# owl_digital.net
KiCad netlist of a schematic drawn in EAGLE
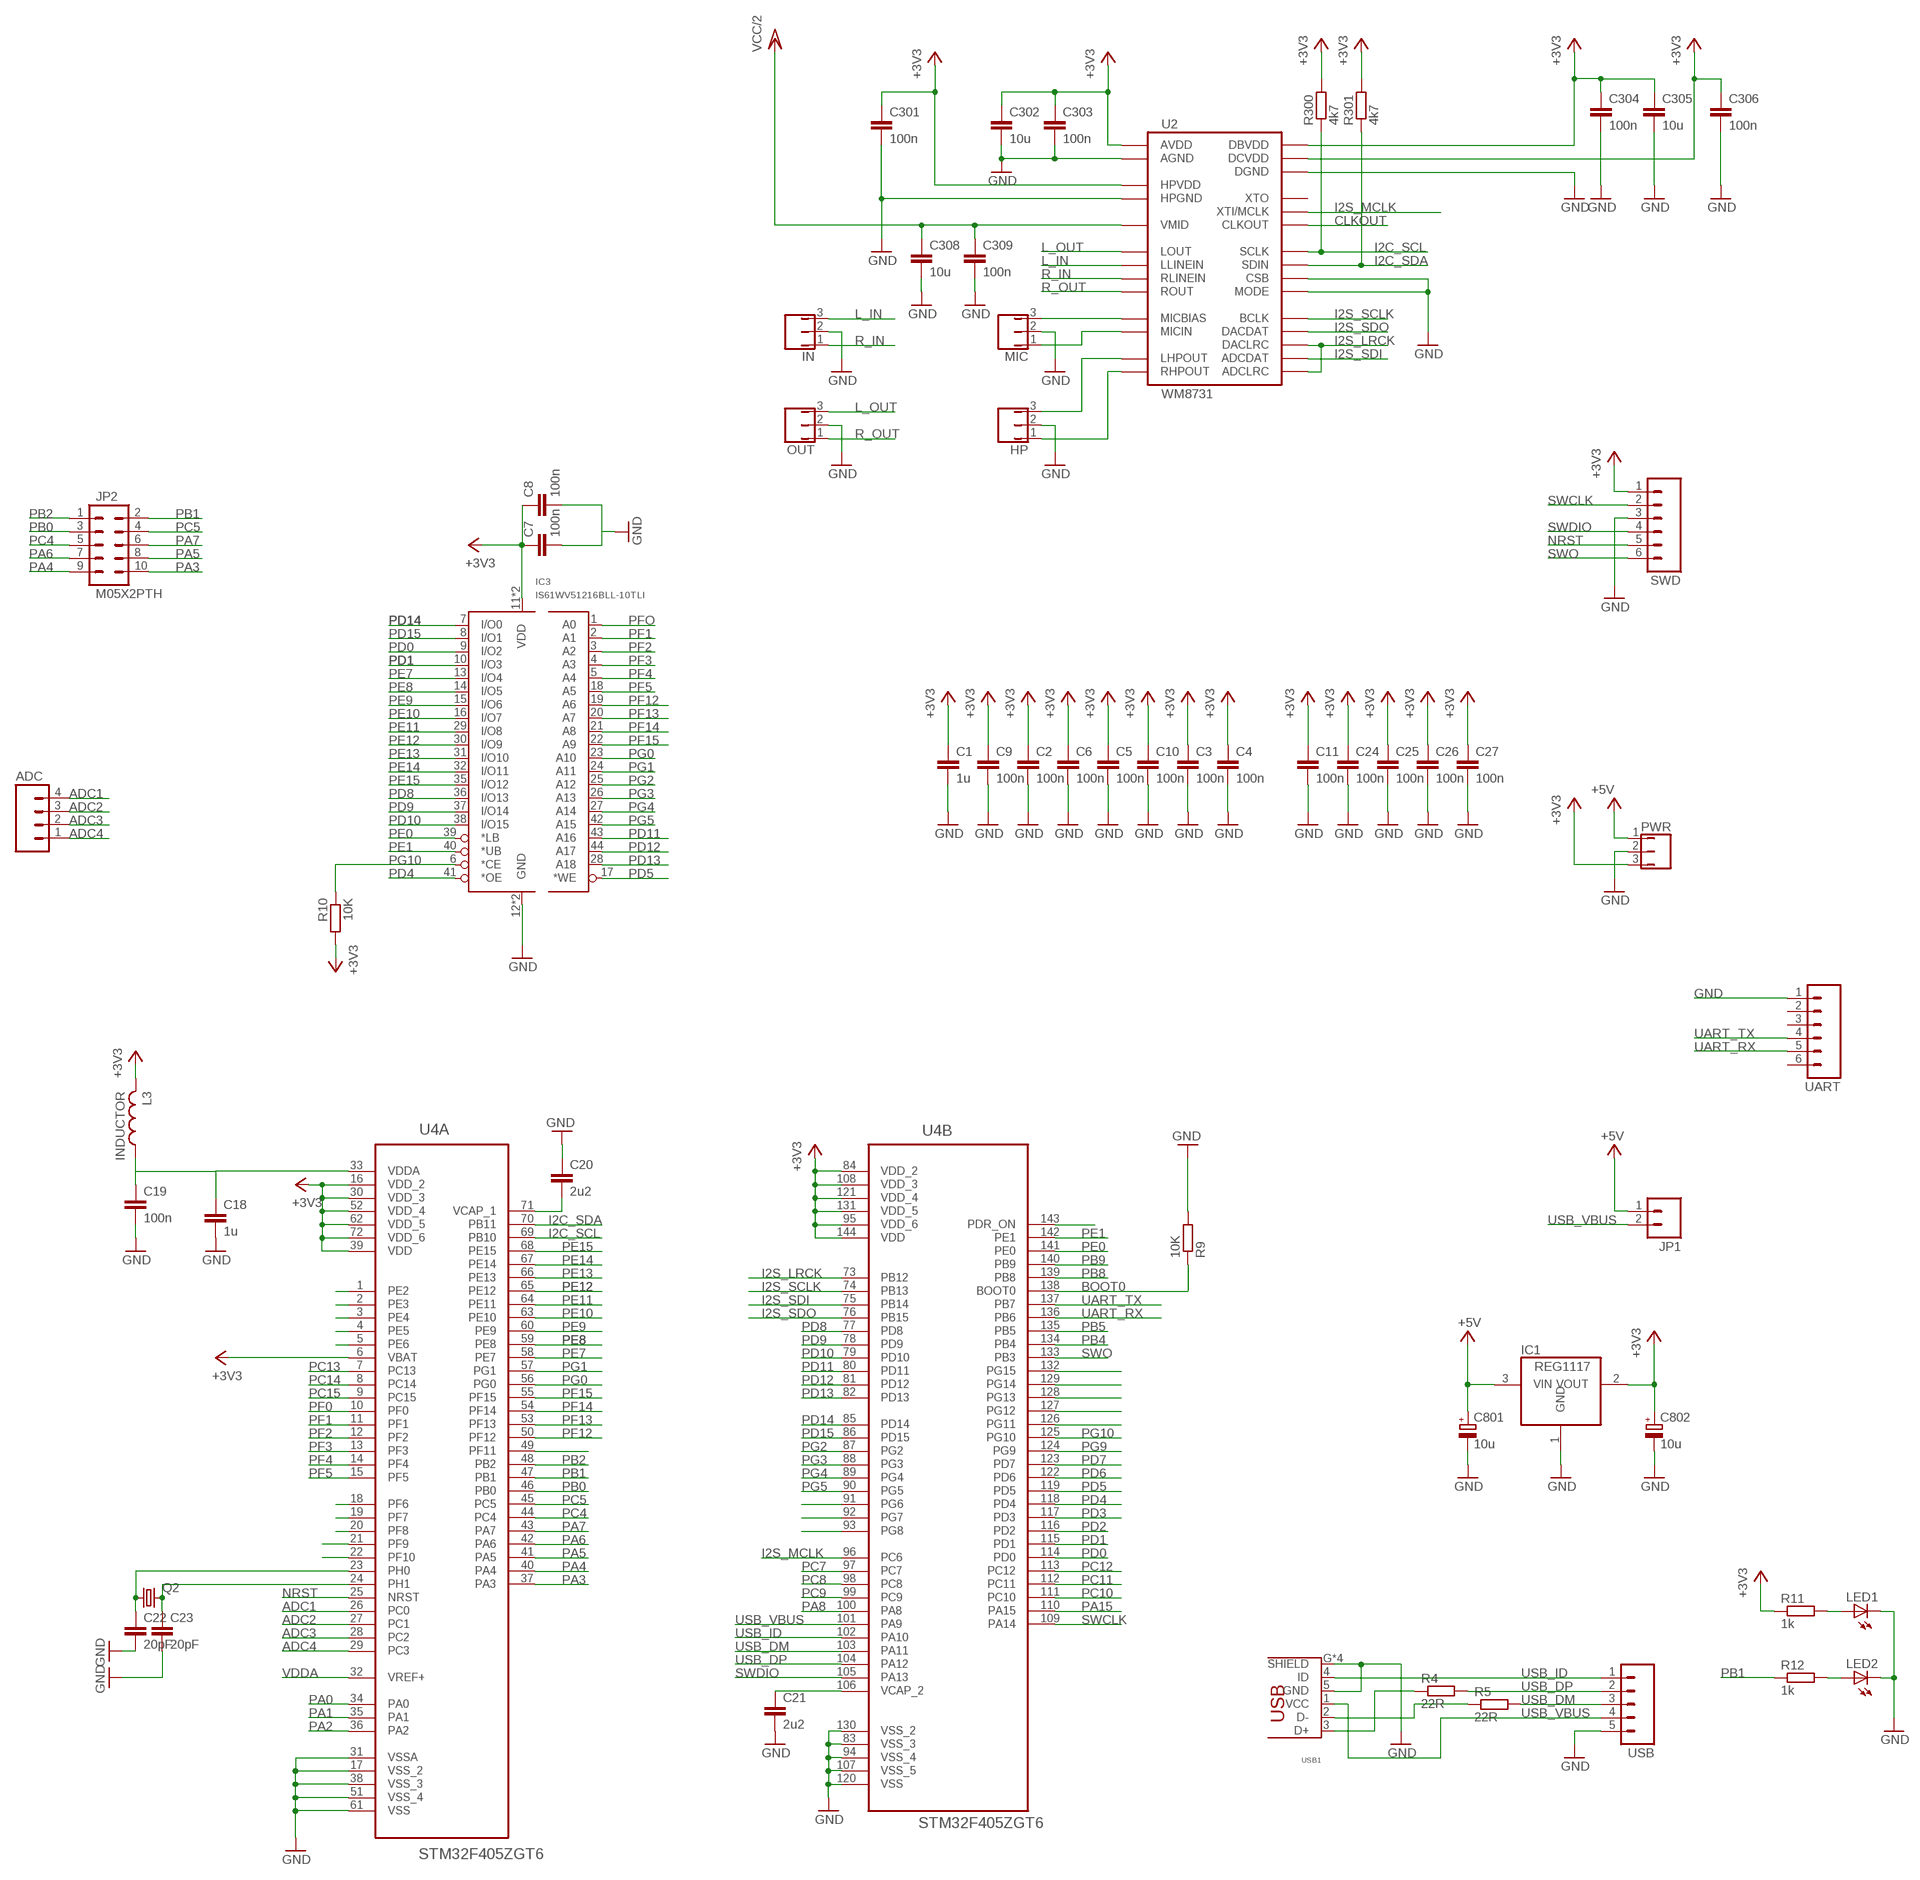
[diagram p0: schematic, sheet 1]

(export (version "E")
  (design (tool "Eeschema 10.0.6"))
  (components
    (comp (ref "ADC")
      (value "M04PTH")
      (footprint "eagle-import:1X04")
      (libsource (lib "eagle-import") (part "M04PTH"))
    )
    (comp (ref "C1")
      (value "1u")
      (footprint "eagle-import:C0603")
      (libsource (lib "eagle-import") (part "C-EUC0603"))
    )
    (comp (ref "C2")
      (value "100n")
      (footprint "eagle-import:C0603")
      (libsource (lib "eagle-import") (part "C-EUC0603"))
    )
    (comp (ref "C3")
      (value "100n")
      (footprint "eagle-import:C0603")
      (libsource (lib "eagle-import") (part "C-EUC0603"))
    )
    (comp (ref "C4")
      (value "100n")
      (footprint "eagle-import:C0603")
      (libsource (lib "eagle-import") (part "C-EUC0603"))
    )
    (comp (ref "C5")
      (value "100n")
      (footprint "eagle-import:C0603")
      (libsource (lib "eagle-import") (part "C-EUC0603"))
    )
    (comp (ref "C6")
      (value "100n")
      (footprint "eagle-import:C0603")
      (libsource (lib "eagle-import") (part "C-EUC0603"))
    )
    (comp (ref "C7")
      (value "100n")
      (footprint "eagle-import:C0603")
      (libsource (lib "eagle-import") (part "C-EUC0603"))
    )
    (comp (ref "C8")
      (value "100n")
      (footprint "eagle-import:C0603")
      (libsource (lib "eagle-import") (part "C-EUC0603"))
    )
    (comp (ref "C9")
      (value "100n")
      (footprint "eagle-import:C0603")
      (libsource (lib "eagle-import") (part "C-EUC0603"))
    )
    (comp (ref "C10")
      (value "100n")
      (footprint "eagle-import:C0603")
      (libsource (lib "eagle-import") (part "C-EUC0603"))
    )
    (comp (ref "C11")
      (value "100n")
      (footprint "eagle-import:C0603")
      (libsource (lib "eagle-import") (part "C-EUC0603"))
    )
    (comp (ref "C18")
      (value "1u")
      (footprint "eagle-import:C0603")
      (libsource (lib "eagle-import") (part "C-EUC0603"))
    )
    (comp (ref "C19")
      (value "100n")
      (footprint "eagle-import:C0603")
      (libsource (lib "eagle-import") (part "C-EUC0603"))
    )
    (comp (ref "C20")
      (value "2u2")
      (footprint "eagle-import:C0603")
      (libsource (lib "eagle-import") (part "C-EUC0603"))
    )
    (comp (ref "C21")
      (value "2u2")
      (footprint "eagle-import:C0603")
      (libsource (lib "eagle-import") (part "C-EUC0603"))
    )
    (comp (ref "C22")
      (value "20pF")
      (footprint "eagle-import:C0603")
      (libsource (lib "eagle-import") (part "C-EUC0603"))
    )
    (comp (ref "C23")
      (value "20pF")
      (footprint "eagle-import:C0603")
      (libsource (lib "eagle-import") (part "C-EUC0603"))
    )
    (comp (ref "C24")
      (value "100n")
      (footprint "eagle-import:C0603")
      (libsource (lib "eagle-import") (part "C-EUC0603"))
    )
    (comp (ref "C25")
      (value "100n")
      (footprint "eagle-import:C0603")
      (libsource (lib "eagle-import") (part "C-EUC0603"))
    )
    (comp (ref "C26")
      (value "100n")
      (footprint "eagle-import:C0603")
      (libsource (lib "eagle-import") (part "C-EUC0603"))
    )
    (comp (ref "C27")
      (value "100n")
      (footprint "eagle-import:C0603")
      (libsource (lib "eagle-import") (part "C-EUC0603"))
    )
    (comp (ref "C301")
      (value "100n")
      (footprint "eagle-import:C0603")
      (libsource (lib "eagle-import") (part "C-EUC0603"))
    )
    (comp (ref "C302")
      (value "10u")
      (footprint "eagle-import:C1206")
      (libsource (lib "eagle-import") (part "C-EUC1206"))
    )
    (comp (ref "C303")
      (value "100n")
      (footprint "eagle-import:C0603")
      (libsource (lib "eagle-import") (part "C-EUC0603"))
    )
    (comp (ref "C304")
      (value "100n")
      (footprint "eagle-import:C0603")
      (libsource (lib "eagle-import") (part "C-EUC0603"))
    )
    (comp (ref "C305")
      (value "10u")
      (footprint "eagle-import:C1206")
      (libsource (lib "eagle-import") (part "C-EUC1206"))
    )
    (comp (ref "C306")
      (value "100n")
      (footprint "eagle-import:C0603")
      (libsource (lib "eagle-import") (part "C-EUC0603"))
    )
    (comp (ref "C308")
      (value "10u")
      (footprint "eagle-import:C1206")
      (libsource (lib "eagle-import") (part "C-EUC1206"))
    )
    (comp (ref "C309")
      (value "100n")
      (footprint "eagle-import:C0603")
      (libsource (lib "eagle-import") (part "C-EUC0603"))
    )
    (comp (ref "C801")
      (value "10u")
      (footprint "eagle-import:PANASONIC_A")
      (libsource (lib "eagle-import") (part "CPOL-EUA"))
    )
    (comp (ref "C802")
      (value "10u")
      (footprint "eagle-import:PANASONIC_A")
      (libsource (lib "eagle-import") (part "CPOL-EUA"))
    )
    (comp (ref "HP")
      (value "JMP/3P/SIP")
      (footprint "eagle-import:JMP_3P_SIP")
      (libsource (lib "eagle-import") (part "JMP/3P/SIP"))
    )
    (comp (ref "IC1")
      (value "REG1117")
      (footprint "eagle-import:SOT223")
      (libsource (lib "eagle-import") (part "REG1117"))
    )
    (comp (ref "IC3")
      (value "IS61WV51216BLL-10TLI")
      (footprint "eagle-import:TSOP44-II")
      (libsource (lib "eagle-import") (part "IS61WV51216BLL-10TLI"))
    )
    (comp (ref "IN")
      (value "JMP/3P/SIP")
      (footprint "eagle-import:JMP_3P_SIP")
      (libsource (lib "eagle-import") (part "JMP/3P/SIP"))
    )
    (comp (ref "JP1")
      (value "M02PTH")
      (footprint "eagle-import:1X02")
      (libsource (lib "eagle-import") (part "M02PTH"))
    )
    (comp (ref "JP2")
      (value "M05X2PTH")
      (footprint "eagle-import:AVR_ICSP")
      (libsource (lib "eagle-import") (part "M05X2PTH"))
    )
    (comp (ref "L3")
      (value "INDUCTOR")
      (footprint "eagle-import:0603")
      (libsource (lib "eagle-import") (part "INDUCTOR"))
    )
    (comp (ref "LED1")
      (value "LED1206")
      (footprint "eagle-import:LED-1206")
      (libsource (lib "eagle-import") (part "LED1206"))
    )
    (comp (ref "LED2")
      (value "LED1206")
      (footprint "eagle-import:LED-1206")
      (libsource (lib "eagle-import") (part "LED1206"))
    )
    (comp (ref "MIC")
      (value "JMP/3P/SIP")
      (footprint "eagle-import:JMP_3P_SIP")
      (libsource (lib "eagle-import") (part "JMP/3P/SIP"))
    )
    (comp (ref "OUT")
      (value "JMP/3P/SIP")
      (footprint "eagle-import:JMP_3P_SIP")
      (libsource (lib "eagle-import") (part "JMP/3P/SIP"))
    )
    (comp (ref "PWR")
      (value "JMP/3P/SIP")
      (footprint "eagle-import:JMP_3P_SIP")
      (libsource (lib "eagle-import") (part "JMP/3P/SIP"))
    )
    (comp (ref "Q2")
      (value "CRYSTALHC49UP")
      (footprint "eagle-import:HC49UP")
      (libsource (lib "eagle-import") (part "CRYSTALHC49UP"))
    )
    (comp (ref "R4")
      (value "22R")
      (footprint "eagle-import:R0603")
      (libsource (lib "eagle-import") (part "R-EU_R0603"))
    )
    (comp (ref "R5")
      (value "22R")
      (footprint "eagle-import:R0603")
      (libsource (lib "eagle-import") (part "R-EU_R0603"))
    )
    (comp (ref "R9")
      (value "10K")
      (footprint "eagle-import:R0603")
      (libsource (lib "eagle-import") (part "R-EU_R0603"))
    )
    (comp (ref "R10")
      (value "10K")
      (footprint "eagle-import:R0603")
      (libsource (lib "eagle-import") (part "R-EU_R0603"))
    )
    (comp (ref "R11")
      (value "1k")
      (footprint "eagle-import:R0603")
      (libsource (lib "eagle-import") (part "R-EU_R0603"))
    )
    (comp (ref "R12")
      (value "1k")
      (footprint "eagle-import:R0603")
      (libsource (lib "eagle-import") (part "R-EU_R0603"))
    )
    (comp (ref "R300")
      (value "4k7")
      (footprint "eagle-import:R0603")
      (libsource (lib "eagle-import") (part "R-EU_R0603"))
    )
    (comp (ref "R301")
      (value "4k7")
      (footprint "eagle-import:R0603")
      (libsource (lib "eagle-import") (part "R-EU_R0603"))
    )
    (comp (ref "SWD")
      (value "M06SIP")
      (footprint "eagle-import:1X06")
      (libsource (lib "eagle-import") (part "M06SIP"))
    )
    (comp (ref "U2")
      (value "WM8731")
      (footprint "eagle-import:28-SSOP")
      (libsource (lib "eagle-import") (part "WM8731"))
    )
    (comp (ref "U4")
      (value "STM32F405ZGT6")
      (footprint "eagle-import:QFP50P2200X2200X160-144N")
      (libsource (lib "eagle-import") (part "STM32F405ZGT6"))
    )
    (comp (ref "UART")
      (value "M06SIP")
      (footprint "eagle-import:1X06")
      (libsource (lib "eagle-import") (part "M06SIP"))
    )
    (comp (ref "USB")
      (value "M05PTH")
      (footprint "eagle-import:1X05")
      (libsource (lib "eagle-import") (part "M05PTH"))
    )
    (comp (ref "USB1")
      (value "USB_HRS_ZX62-B-5PA(11)MICRO.B-")
      (footprint "eagle-import:HRS_ZX62D-AB-5P8_USB")
      (libsource (lib "eagle-import") (part "USB_HRS_ZX62-B-5PA(11)MICRO.B-"))
    )
  )
  (nets
    (net (code "1") (name "+3V3") (class "Default")
      (node (ref "C1") (pin "1") (pinfunction "1_1") (pintype "passive"))
      (node (ref "C10") (pin "1") (pinfunction "1_1") (pintype "passive"))
      (node (ref "C11") (pin "1") (pinfunction "1_1") (pintype "passive"))
      (node (ref "C2") (pin "1") (pinfunction "1_1") (pintype "passive"))
      (node (ref "C24") (pin "1") (pinfunction "1_1") (pintype "passive"))
      (node (ref "C25") (pin "1") (pinfunction "1_1") (pintype "passive"))
      (node (ref "C26") (pin "1") (pinfunction "1_1") (pintype "passive"))
      (node (ref "C27") (pin "1") (pinfunction "1_1") (pintype "passive"))
      (node (ref "C3") (pin "1") (pinfunction "1_1") (pintype "passive"))
      (node (ref "C301") (pin "1") (pinfunction "1_1") (pintype "passive"))
      (node (ref "C302") (pin "1") (pinfunction "1_1") (pintype "passive"))
      (node (ref "C303") (pin "1") (pinfunction "1_1") (pintype "passive"))
      (node (ref "C304") (pin "1") (pinfunction "1_1") (pintype "passive"))
      (node (ref "C305") (pin "1") (pinfunction "1_1") (pintype "passive"))
      (node (ref "C306") (pin "1") (pinfunction "1_1") (pintype "passive"))
      (node (ref "C4") (pin "1") (pinfunction "1_1") (pintype "passive"))
      (node (ref "C5") (pin "1") (pinfunction "1_1") (pintype "passive"))
      (node (ref "C6") (pin "1") (pinfunction "1_1") (pintype "passive"))
      (node (ref "C7") (pin "1") (pinfunction "1_1") (pintype "passive"))
      (node (ref "C8") (pin "1") (pinfunction "1_1") (pintype "passive"))
      (node (ref "C802") (pin "+") (pinfunction "+_+") (pintype "passive"))
      (node (ref "C9") (pin "1") (pinfunction "1_1") (pintype "passive"))
      (node (ref "IC1") (pin "2") (pinfunction "VOUT_2") (pintype "output"))
      (node (ref "IC3") (pin "11") (pinfunction "VDD_11") (pintype "power_in"))
      (node (ref "IC3") (pin "33") (pinfunction "VDD_33") (pintype "power_in"))
      (node (ref "L3") (pin "2") (pinfunction "2_2") (pintype "passive"))
      (node (ref "PWR") (pin "3") (pinfunction "3_3") (pintype "passive"))
      (node (ref "R10") (pin "2") (pinfunction "2_2") (pintype "passive"))
      (node (ref "R11") (pin "1") (pinfunction "1_1") (pintype "passive"))
      (node (ref "R300") (pin "2") (pinfunction "2_2") (pintype "passive"))
      (node (ref "R301") (pin "2") (pinfunction "2_2") (pintype "passive"))
      (node (ref "SWD") (pin "1") (pinfunction "1_1") (pintype "passive"))
      (node (ref "U2") (pin "P$1") (pinfunction "DBVDD_P$1") (pintype "power_in"))
      (node (ref "U2") (pin "P$14") (pinfunction "AVDD_P$14") (pintype "power_in"))
      (node (ref "U2") (pin "P$27") (pinfunction "DCVDD_P$27") (pintype "power_in"))
      (node (ref "U2") (pin "P$8") (pinfunction "HPVDD_P$8") (pintype "power_in"))
      (node (ref "U4") (pin "108") (pinfunction "VDD_3_108") (pintype "power_in"))
      (node (ref "U4") (pin "121") (pinfunction "VDD_4_121") (pintype "power_in"))
      (node (ref "U4") (pin "131") (pinfunction "VDD_5_131") (pintype "power_in"))
      (node (ref "U4") (pin "144") (pinfunction "VDD_144") (pintype "power_in"))
      (node (ref "U4") (pin "16") (pinfunction "VDD_2_16") (pintype "power_in"))
      (node (ref "U4") (pin "30") (pinfunction "VDD_3_30") (pintype "power_in"))
      (node (ref "U4") (pin "39") (pinfunction "VDD_39") (pintype "power_in"))
      (node (ref "U4") (pin "52") (pinfunction "VDD_4_52") (pintype "power_in"))
      (node (ref "U4") (pin "6") (pinfunction "VBAT_6") (pintype "passive"))
      (node (ref "U4") (pin "62") (pinfunction "VDD_5_62") (pintype "power_in"))
      (node (ref "U4") (pin "72") (pinfunction "VDD_6_72") (pintype "power_in"))
      (node (ref "U4") (pin "84") (pinfunction "VDD_2_84") (pintype "power_in"))
      (node (ref "U4") (pin "95") (pinfunction "VDD_6_95") (pintype "power_in"))
    )
    (net (code "2") (name "+5V") (class "Default")
      (node (ref "C801") (pin "+") (pinfunction "+_+") (pintype "passive"))
      (node (ref "IC1") (pin "3") (pinfunction "VIN_3") (pintype "input"))
      (node (ref "JP1") (pin "1") (pinfunction "1_1") (pintype "passive"))
      (node (ref "PWR") (pin "1") (pinfunction "1_1") (pintype "passive"))
    )
    (net (code "3") (name "/ADC1") (class "Default")
      (node (ref "ADC") (pin "4") (pinfunction "4_4") (pintype "passive"))
      (node (ref "U4") (pin "26") (pinfunction "PC0_26") (pintype "bidirectional"))
    )
    (net (code "4") (name "/ADC2") (class "Default")
      (node (ref "ADC") (pin "3") (pinfunction "3_3") (pintype "passive"))
      (node (ref "U4") (pin "27") (pinfunction "PC1_27") (pintype "bidirectional"))
    )
    (net (code "5") (name "/ADC3") (class "Default")
      (node (ref "ADC") (pin "2") (pinfunction "2_2") (pintype "passive"))
      (node (ref "U4") (pin "28") (pinfunction "PC2_28") (pintype "bidirectional"))
    )
    (net (code "6") (name "/ADC4") (class "Default")
      (node (ref "ADC") (pin "1") (pinfunction "1_1") (pintype "passive"))
      (node (ref "U4") (pin "29") (pinfunction "PC3_29") (pintype "bidirectional"))
    )
    (net (code "7") (name "/BOOT0") (class "Default")
      (node (ref "R9") (pin "1") (pinfunction "1_1") (pintype "passive"))
      (node (ref "U4") (pin "138") (pinfunction "BOOT0_138") (pintype "passive"))
    )
    (net (code "8") (name "/CLKOUT") (class "Default")
      (node (ref "U2") (pin "P$2") (pinfunction "CLKOUT_P$2") (pintype "output"))
    )
    (net (code "9") (name "/I2C_SCL") (class "Default")
      (node (ref "R300") (pin "1") (pinfunction "1_1") (pintype "passive"))
      (node (ref "U2") (pin "P$24") (pinfunction "SCLK_P$24") (pintype "input"))
      (node (ref "U4") (pin "69") (pinfunction "PB10_69") (pintype "bidirectional"))
    )
    (net (code "10") (name "/I2C_SDA") (class "Default")
      (node (ref "R301") (pin "1") (pinfunction "1_1") (pintype "passive"))
      (node (ref "U2") (pin "P$23") (pinfunction "SDIN_P$23") (pintype "bidirectional"))
      (node (ref "U4") (pin "70") (pinfunction "PB11_70") (pintype "bidirectional"))
    )
    (net (code "11") (name "/I2S_LRCK") (class "Default")
      (node (ref "U2") (pin "P$5") (pinfunction "DACLRC_P$5") (pintype "bidirectional"))
      (node (ref "U2") (pin "P$7") (pinfunction "ADCLRC_P$7") (pintype "bidirectional"))
      (node (ref "U4") (pin "73") (pinfunction "PB12_73") (pintype "bidirectional"))
    )
    (net (code "12") (name "/I2S_MCLK") (class "Default")
      (node (ref "U2") (pin "P$25") (pinfunction "XTI/MCLK_P$25") (pintype "input"))
      (node (ref "U4") (pin "96") (pinfunction "PC6_96") (pintype "bidirectional"))
    )
    (net (code "13") (name "/I2S_SCLK") (class "Default")
      (node (ref "U2") (pin "P$3") (pinfunction "BCLK_P$3") (pintype "bidirectional"))
      (node (ref "U4") (pin "74") (pinfunction "PB13_74") (pintype "bidirectional"))
    )
    (net (code "14") (name "/I2S_SDI") (class "Default")
      (node (ref "U2") (pin "P$6") (pinfunction "ADCDAT_P$6") (pintype "output"))
      (node (ref "U4") (pin "75") (pinfunction "PB14_75") (pintype "bidirectional"))
    )
    (net (code "15") (name "/I2S_SDO") (class "Default")
      (node (ref "U2") (pin "P$4") (pinfunction "DACDAT_P$4") (pintype "input"))
      (node (ref "U4") (pin "76") (pinfunction "PB15_76") (pintype "bidirectional"))
    )
    (net (code "16") (name "/L_IN") (class "Default")
      (node (ref "IN") (pin "3") (pinfunction "3_3") (pintype "passive"))
      (node (ref "U2") (pin "P$20") (pinfunction "LLINEIN_P$20") (pintype "input"))
    )
    (net (code "17") (name "/L_OUT") (class "Default")
      (node (ref "OUT") (pin "3") (pinfunction "3_3") (pintype "passive"))
      (node (ref "U2") (pin "P$12") (pinfunction "LOUT_P$12") (pintype "output"))
    )
    (net (code "18") (name "/NRST") (class "Default")
      (node (ref "SWD") (pin "5") (pinfunction "5_5") (pintype "passive"))
      (node (ref "U4") (pin "25") (pinfunction "NRST_25") (pintype "passive"))
    )
    (net (code "19") (name "/PA0") (class "Default")
      (node (ref "U4") (pin "34") (pinfunction "PA0_34") (pintype "bidirectional"))
    )
    (net (code "20") (name "/PA1") (class "Default")
      (node (ref "U4") (pin "35") (pinfunction "PA1_35") (pintype "bidirectional"))
    )
    (net (code "21") (name "/PA2") (class "Default")
      (node (ref "U4") (pin "36") (pinfunction "PA2_36") (pintype "bidirectional"))
    )
    (net (code "22") (name "/PA3") (class "Default")
      (node (ref "JP2") (pin "10") (pinfunction "10_10") (pintype "passive"))
      (node (ref "U4") (pin "37") (pinfunction "PA3_37") (pintype "bidirectional"))
    )
    (net (code "23") (name "/PA4") (class "Default")
      (node (ref "JP2") (pin "9") (pinfunction "9_9") (pintype "passive"))
      (node (ref "U4") (pin "40") (pinfunction "PA4_40") (pintype "bidirectional"))
    )
    (net (code "24") (name "/PA5") (class "Default")
      (node (ref "JP2") (pin "8") (pinfunction "8_8") (pintype "passive"))
      (node (ref "U4") (pin "41") (pinfunction "PA5_41") (pintype "bidirectional"))
    )
    (net (code "25") (name "/PA6") (class "Default")
      (node (ref "JP2") (pin "7") (pinfunction "7_7") (pintype "passive"))
      (node (ref "U4") (pin "42") (pinfunction "PA6_42") (pintype "bidirectional"))
    )
    (net (code "26") (name "/PA7") (class "Default")
      (node (ref "JP2") (pin "6") (pinfunction "6_6") (pintype "passive"))
      (node (ref "U4") (pin "43") (pinfunction "PA7_43") (pintype "bidirectional"))
    )
    (net (code "27") (name "/PA8") (class "Default")
      (node (ref "U4") (pin "100") (pinfunction "PA8_100") (pintype "bidirectional"))
    )
    (net (code "28") (name "/PA15") (class "Default")
      (node (ref "U4") (pin "110") (pinfunction "PA15_110") (pintype "bidirectional"))
    )
    (net (code "29") (name "/PB0") (class "Default")
      (node (ref "JP2") (pin "3") (pinfunction "3_3") (pintype "passive"))
      (node (ref "U4") (pin "46") (pinfunction "PB0_46") (pintype "bidirectional"))
    )
    (net (code "30") (name "/PB1") (class "Default")
      (node (ref "JP2") (pin "2") (pinfunction "2_2") (pintype "passive"))
      (node (ref "R12") (pin "1") (pinfunction "1_1") (pintype "passive"))
      (node (ref "U4") (pin "47") (pinfunction "PB1_47") (pintype "bidirectional"))
    )
    (net (code "31") (name "/PB2") (class "Default")
      (node (ref "JP2") (pin "1") (pinfunction "1_1") (pintype "passive"))
      (node (ref "U4") (pin "48") (pinfunction "PB2_48") (pintype "bidirectional"))
    )
    (net (code "32") (name "/PB4") (class "Default")
      (node (ref "U4") (pin "134") (pinfunction "PB4_134") (pintype "bidirectional"))
    )
    (net (code "33") (name "/PB5") (class "Default")
      (node (ref "U4") (pin "135") (pinfunction "PB5_135") (pintype "bidirectional"))
    )
    (net (code "34") (name "/PB8") (class "Default")
      (node (ref "U4") (pin "139") (pinfunction "PB8_139") (pintype "bidirectional"))
    )
    (net (code "35") (name "/PB9") (class "Default")
      (node (ref "U4") (pin "140") (pinfunction "PB9_140") (pintype "bidirectional"))
    )
    (net (code "36") (name "/PC4") (class "Default")
      (node (ref "JP2") (pin "5") (pinfunction "5_5") (pintype "passive"))
      (node (ref "U4") (pin "44") (pinfunction "PC4_44") (pintype "bidirectional"))
    )
    (net (code "37") (name "/PC5") (class "Default")
      (node (ref "JP2") (pin "4") (pinfunction "4_4") (pintype "passive"))
      (node (ref "U4") (pin "45") (pinfunction "PC5_45") (pintype "bidirectional"))
    )
    (net (code "38") (name "/PC7") (class "Default")
      (node (ref "U4") (pin "97") (pinfunction "PC7_97") (pintype "bidirectional"))
    )
    (net (code "39") (name "/PC8") (class "Default")
      (node (ref "U4") (pin "98") (pinfunction "PC8_98") (pintype "bidirectional"))
    )
    (net (code "40") (name "/PC9") (class "Default")
      (node (ref "U4") (pin "99") (pinfunction "PC9_99") (pintype "bidirectional"))
    )
    (net (code "41") (name "/PC10") (class "Default")
      (node (ref "U4") (pin "111") (pinfunction "PC10_111") (pintype "bidirectional"))
    )
    (net (code "42") (name "/PC11") (class "Default")
      (node (ref "U4") (pin "112") (pinfunction "PC11_112") (pintype "bidirectional"))
    )
    (net (code "43") (name "/PC12") (class "Default")
      (node (ref "U4") (pin "113") (pinfunction "PC12_113") (pintype "bidirectional"))
    )
    (net (code "44") (name "/PC13") (class "Default")
      (node (ref "U4") (pin "7") (pinfunction "PC13_7") (pintype "bidirectional"))
    )
    (net (code "45") (name "/PC14") (class "Default")
      (node (ref "U4") (pin "8") (pinfunction "PC14_8") (pintype "bidirectional"))
    )
    (net (code "46") (name "/PC15") (class "Default")
      (node (ref "U4") (pin "9") (pinfunction "PC15_9") (pintype "bidirectional"))
    )
    (net (code "47") (name "/PD0") (class "Default")
      (node (ref "IC3") (pin "9") (pinfunction "I/O2_9") (pintype "bidirectional"))
      (node (ref "U4") (pin "114") (pinfunction "PD0_114") (pintype "bidirectional"))
    )
    (net (code "48") (name "/PD1") (class "Default")
      (node (ref "IC3") (pin "10") (pinfunction "I/O3_10") (pintype "bidirectional"))
      (node (ref "U4") (pin "115") (pinfunction "PD1_115") (pintype "bidirectional"))
    )
    (net (code "49") (name "/PD2") (class "Default")
      (node (ref "U4") (pin "116") (pinfunction "PD2_116") (pintype "bidirectional"))
    )
    (net (code "50") (name "/PD3") (class "Default")
      (node (ref "U4") (pin "117") (pinfunction "PD3_117") (pintype "bidirectional"))
    )
    (net (code "51") (name "/PD4") (class "Default")
      (node (ref "IC3") (pin "41") (pinfunction "*OE_41") (pintype "bidirectional"))
      (node (ref "U4") (pin "118") (pinfunction "PD4_118") (pintype "bidirectional"))
    )
    (net (code "52") (name "/PD5") (class "Default")
      (node (ref "IC3") (pin "17") (pinfunction "*WE_17") (pintype "bidirectional"))
      (node (ref "U4") (pin "119") (pinfunction "PD5_119") (pintype "bidirectional"))
    )
    (net (code "53") (name "/PD6") (class "Default")
      (node (ref "U4") (pin "122") (pinfunction "PD6_122") (pintype "bidirectional"))
    )
    (net (code "54") (name "/PD7") (class "Default")
      (node (ref "U4") (pin "123") (pinfunction "PD7_123") (pintype "bidirectional"))
    )
    (net (code "55") (name "/PD8") (class "Default")
      (node (ref "IC3") (pin "36") (pinfunction "I/O13_36") (pintype "bidirectional"))
      (node (ref "U4") (pin "77") (pinfunction "PD8_77") (pintype "bidirectional"))
    )
    (net (code "56") (name "/PD9") (class "Default")
      (node (ref "IC3") (pin "37") (pinfunction "I/O14_37") (pintype "bidirectional"))
      (node (ref "U4") (pin "78") (pinfunction "PD9_78") (pintype "bidirectional"))
    )
    (net (code "57") (name "/PD10") (class "Default")
      (node (ref "IC3") (pin "38") (pinfunction "I/O15_38") (pintype "bidirectional"))
      (node (ref "U4") (pin "79") (pinfunction "PD10_79") (pintype "bidirectional"))
    )
    (net (code "58") (name "/PD11") (class "Default")
      (node (ref "IC3") (pin "43") (pinfunction "A16_43") (pintype "input"))
      (node (ref "U4") (pin "80") (pinfunction "PD11_80") (pintype "bidirectional"))
    )
    (net (code "59") (name "/PD12") (class "Default")
      (node (ref "IC3") (pin "44") (pinfunction "A17_44") (pintype "input"))
      (node (ref "U4") (pin "81") (pinfunction "PD12_81") (pintype "bidirectional"))
    )
    (net (code "60") (name "/PD13") (class "Default")
      (node (ref "IC3") (pin "28") (pinfunction "A18_28") (pintype "input"))
      (node (ref "U4") (pin "82") (pinfunction "PD13_82") (pintype "bidirectional"))
    )
    (net (code "61") (name "/PD14") (class "Default")
      (node (ref "IC3") (pin "7") (pinfunction "I/O0_7") (pintype "bidirectional"))
      (node (ref "U4") (pin "85") (pinfunction "PD14_85") (pintype "bidirectional"))
    )
    (net (code "62") (name "/PD15") (class "Default")
      (node (ref "IC3") (pin "8") (pinfunction "I/O1_8") (pintype "bidirectional"))
      (node (ref "U4") (pin "86") (pinfunction "PD15_86") (pintype "bidirectional"))
    )
    (net (code "63") (name "/PE0") (class "Default")
      (node (ref "IC3") (pin "39") (pinfunction "*LB_39") (pintype "bidirectional"))
      (node (ref "U4") (pin "141") (pinfunction "PE0_141") (pintype "bidirectional"))
    )
    (net (code "64") (name "/PE1") (class "Default")
      (node (ref "IC3") (pin "40") (pinfunction "*UB_40") (pintype "bidirectional"))
      (node (ref "U4") (pin "142") (pinfunction "PE1_142") (pintype "bidirectional"))
    )
    (net (code "65") (name "/PE7") (class "Default")
      (node (ref "IC3") (pin "13") (pinfunction "I/O4_13") (pintype "bidirectional"))
      (node (ref "U4") (pin "58") (pinfunction "PE7_58") (pintype "bidirectional"))
    )
    (net (code "66") (name "/PE8") (class "Default")
      (node (ref "IC3") (pin "14") (pinfunction "I/O5_14") (pintype "bidirectional"))
      (node (ref "U4") (pin "59") (pinfunction "PE8_59") (pintype "bidirectional"))
    )
    (net (code "67") (name "/PE9") (class "Default")
      (node (ref "IC3") (pin "15") (pinfunction "I/O6_15") (pintype "bidirectional"))
      (node (ref "U4") (pin "60") (pinfunction "PE9_60") (pintype "bidirectional"))
    )
    (net (code "68") (name "/PE10") (class "Default")
      (node (ref "IC3") (pin "16") (pinfunction "I/O7_16") (pintype "bidirectional"))
      (node (ref "U4") (pin "63") (pinfunction "PE10_63") (pintype "bidirectional"))
    )
    (net (code "69") (name "/PE11") (class "Default")
      (node (ref "IC3") (pin "29") (pinfunction "I/O8_29") (pintype "bidirectional"))
      (node (ref "U4") (pin "64") (pinfunction "PE11_64") (pintype "bidirectional"))
    )
    (net (code "70") (name "/PE12") (class "Default")
      (node (ref "IC3") (pin "30") (pinfunction "I/O9_30") (pintype "bidirectional"))
      (node (ref "U4") (pin "65") (pinfunction "PE12_65") (pintype "bidirectional"))
    )
    (net (code "71") (name "/PE13") (class "Default")
      (node (ref "IC3") (pin "31") (pinfunction "I/O10_31") (pintype "bidirectional"))
      (node (ref "U4") (pin "66") (pinfunction "PE13_66") (pintype "bidirectional"))
    )
    (net (code "72") (name "/PE14") (class "Default")
      (node (ref "IC3") (pin "32") (pinfunction "I/O11_32") (pintype "bidirectional"))
      (node (ref "U4") (pin "67") (pinfunction "PE14_67") (pintype "bidirectional"))
    )
    (net (code "73") (name "/PE15") (class "Default")
      (node (ref "IC3") (pin "35") (pinfunction "I/O12_35") (pintype "bidirectional"))
      (node (ref "U4") (pin "68") (pinfunction "PE15_68") (pintype "bidirectional"))
    )
    (net (code "74") (name "/PF0") (class "Default")
      (node (ref "U4") (pin "10") (pinfunction "PF0_10") (pintype "bidirectional"))
    )
    (net (code "75") (name "/PF1") (class "Default")
      (node (ref "IC3") (pin "2") (pinfunction "A1_2") (pintype "input"))
      (node (ref "U4") (pin "11") (pinfunction "PF1_11") (pintype "bidirectional"))
    )
    (net (code "76") (name "/PF2") (class "Default")
      (node (ref "IC3") (pin "3") (pinfunction "A2_3") (pintype "input"))
      (node (ref "U4") (pin "12") (pinfunction "PF2_12") (pintype "bidirectional"))
    )
    (net (code "77") (name "/PF3") (class "Default")
      (node (ref "IC3") (pin "4") (pinfunction "A3_4") (pintype "input"))
      (node (ref "U4") (pin "13") (pinfunction "PF3_13") (pintype "bidirectional"))
    )
    (net (code "78") (name "/PF4") (class "Default")
      (node (ref "IC3") (pin "5") (pinfunction "A4_5") (pintype "input"))
      (node (ref "U4") (pin "14") (pinfunction "PF4_14") (pintype "bidirectional"))
    )
    (net (code "79") (name "/PF5") (class "Default")
      (node (ref "IC3") (pin "18") (pinfunction "A5_18") (pintype "input"))
      (node (ref "U4") (pin "15") (pinfunction "PF5_15") (pintype "bidirectional"))
    )
    (net (code "80") (name "/PF12") (class "Default")
      (node (ref "IC3") (pin "19") (pinfunction "A6_19") (pintype "input"))
      (node (ref "U4") (pin "50") (pinfunction "PF12_50") (pintype "bidirectional"))
    )
    (net (code "81") (name "/PF13") (class "Default")
      (node (ref "IC3") (pin "20") (pinfunction "A7_20") (pintype "input"))
      (node (ref "U4") (pin "53") (pinfunction "PF13_53") (pintype "bidirectional"))
    )
    (net (code "82") (name "/PF14") (class "Default")
      (node (ref "IC3") (pin "21") (pinfunction "A8_21") (pintype "input"))
      (node (ref "U4") (pin "54") (pinfunction "PF14_54") (pintype "bidirectional"))
    )
    (net (code "83") (name "/PF15") (class "Default")
      (node (ref "IC3") (pin "22") (pinfunction "A9_22") (pintype "input"))
      (node (ref "U4") (pin "55") (pinfunction "PF15_55") (pintype "bidirectional"))
    )
    (net (code "84") (name "/PFO") (class "Default")
      (node (ref "IC3") (pin "1") (pinfunction "A0_1") (pintype "input"))
    )
    (net (code "85") (name "/PG0") (class "Default")
      (node (ref "IC3") (pin "23") (pinfunction "A10_23") (pintype "input"))
      (node (ref "U4") (pin "56") (pinfunction "PG0_56") (pintype "bidirectional"))
    )
    (net (code "86") (name "/PG1") (class "Default")
      (node (ref "IC3") (pin "24") (pinfunction "A11_24") (pintype "input"))
      (node (ref "U4") (pin "57") (pinfunction "PG1_57") (pintype "bidirectional"))
    )
    (net (code "87") (name "/PG2") (class "Default")
      (node (ref "IC3") (pin "25") (pinfunction "A12_25") (pintype "input"))
      (node (ref "U4") (pin "87") (pinfunction "PG2_87") (pintype "bidirectional"))
    )
    (net (code "88") (name "/PG3") (class "Default")
      (node (ref "IC3") (pin "26") (pinfunction "A13_26") (pintype "input"))
      (node (ref "U4") (pin "88") (pinfunction "PG3_88") (pintype "bidirectional"))
    )
    (net (code "89") (name "/PG4") (class "Default")
      (node (ref "IC3") (pin "27") (pinfunction "A14_27") (pintype "input"))
      (node (ref "U4") (pin "89") (pinfunction "PG4_89") (pintype "bidirectional"))
    )
    (net (code "90") (name "/PG5") (class "Default")
      (node (ref "IC3") (pin "42") (pinfunction "A15_42") (pintype "input"))
      (node (ref "U4") (pin "90") (pinfunction "PG5_90") (pintype "bidirectional"))
    )
    (net (code "91") (name "/PG9") (class "Default")
      (node (ref "U4") (pin "124") (pinfunction "PG9_124") (pintype "bidirectional"))
    )
    (net (code "92") (name "/PG10") (class "Default")
      (node (ref "IC3") (pin "6") (pinfunction "*CE_6") (pintype "bidirectional"))
      (node (ref "R10") (pin "1") (pinfunction "1_1") (pintype "passive"))
      (node (ref "U4") (pin "125") (pinfunction "PG10_125") (pintype "bidirectional"))
    )
    (net (code "93") (name "/R_IN") (class "Default")
      (node (ref "IN") (pin "1") (pinfunction "1_1") (pintype "passive"))
      (node (ref "U2") (pin "P$19") (pinfunction "RLINEIN_P$19") (pintype "input"))
    )
    (net (code "94") (name "/R_OUT") (class "Default")
      (node (ref "OUT") (pin "1") (pinfunction "1_1") (pintype "passive"))
      (node (ref "U2") (pin "P$13") (pinfunction "ROUT_P$13") (pintype "output"))
    )
    (net (code "95") (name "/SWCLK") (class "Default")
      (node (ref "SWD") (pin "2") (pinfunction "2_2") (pintype "passive"))
      (node (ref "U4") (pin "109") (pinfunction "PA14_109") (pintype "bidirectional"))
    )
    (net (code "96") (name "/SWDIO") (class "Default")
      (node (ref "SWD") (pin "4") (pinfunction "4_4") (pintype "passive"))
      (node (ref "U4") (pin "105") (pinfunction "PA13_105") (pintype "bidirectional"))
    )
    (net (code "97") (name "/SWO") (class "Default")
      (node (ref "SWD") (pin "6") (pinfunction "6_6") (pintype "passive"))
      (node (ref "U4") (pin "133") (pinfunction "PB3_133") (pintype "bidirectional"))
    )
    (net (code "98") (name "/UART_RX") (class "Default")
      (node (ref "U4") (pin "136") (pinfunction "PB6_136") (pintype "bidirectional"))
      (node (ref "UART") (pin "5") (pinfunction "5_5") (pintype "passive"))
    )
    (net (code "99") (name "/UART_TX") (class "Default")
      (node (ref "U4") (pin "137") (pinfunction "PB7_137") (pintype "bidirectional"))
      (node (ref "UART") (pin "4") (pinfunction "4_4") (pintype "passive"))
    )
    (net (code "100") (name "/USB_DM") (class "Default")
      (node (ref "R5") (pin "2") (pinfunction "2_2") (pintype "passive"))
      (node (ref "U4") (pin "103") (pinfunction "PA11_103") (pintype "bidirectional"))
      (node (ref "USB") (pin "3") (pinfunction "3_3") (pintype "passive"))
    )
    (net (code "101") (name "/USB_DP") (class "Default")
      (node (ref "R4") (pin "2") (pinfunction "2_2") (pintype "passive"))
      (node (ref "U4") (pin "104") (pinfunction "PA12_104") (pintype "bidirectional"))
      (node (ref "USB") (pin "2") (pinfunction "2_2") (pintype "passive"))
    )
    (net (code "102") (name "/USB_ID") (class "Default")
      (node (ref "U4") (pin "102") (pinfunction "PA10_102") (pintype "bidirectional"))
      (node (ref "USB") (pin "1") (pinfunction "1_1") (pintype "passive"))
      (node (ref "USB1") (pin "4") (pinfunction "ID_4") (pintype "bidirectional"))
    )
    (net (code "103") (name "/USB_VBUS") (class "Default")
      (node (ref "JP1") (pin "2") (pinfunction "2_2") (pintype "passive"))
      (node (ref "U4") (pin "101") (pinfunction "PA9_101") (pintype "bidirectional"))
      (node (ref "USB") (pin "4") (pinfunction "4_4") (pintype "passive"))
      (node (ref "USB1") (pin "1") (pinfunction "VCC_1") (pintype "bidirectional"))
    )
    (net (code "104") (name "/VDDA") (class "Default")
      (node (ref "C18") (pin "1") (pinfunction "1_1") (pintype "passive"))
      (node (ref "C19") (pin "1") (pinfunction "1_1") (pintype "passive"))
      (node (ref "L3") (pin "1") (pinfunction "1_1") (pintype "passive"))
      (node (ref "U4") (pin "32") (pinfunction "VREF+_32") (pintype "passive"))
      (node (ref "U4") (pin "33") (pinfunction "VDDA_33") (pintype "power_in"))
    )
    (net (code "105") (name "GND") (class "Default")
      (node (ref "C1") (pin "2") (pinfunction "2_2") (pintype "passive"))
      (node (ref "C10") (pin "2") (pinfunction "2_2") (pintype "passive"))
      (node (ref "C11") (pin "2") (pinfunction "2_2") (pintype "passive"))
      (node (ref "C18") (pin "2") (pinfunction "2_2") (pintype "passive"))
      (node (ref "C19") (pin "2") (pinfunction "2_2") (pintype "passive"))
      (node (ref "C2") (pin "2") (pinfunction "2_2") (pintype "passive"))
      (node (ref "C20") (pin "1") (pinfunction "1_1") (pintype "passive"))
      (node (ref "C21") (pin "2") (pinfunction "2_2") (pintype "passive"))
      (node (ref "C22") (pin "2") (pinfunction "2_2") (pintype "passive"))
      (node (ref "C23") (pin "2") (pinfunction "2_2") (pintype "passive"))
      (node (ref "C24") (pin "2") (pinfunction "2_2") (pintype "passive"))
      (node (ref "C25") (pin "2") (pinfunction "2_2") (pintype "passive"))
      (node (ref "C26") (pin "2") (pinfunction "2_2") (pintype "passive"))
      (node (ref "C27") (pin "2") (pinfunction "2_2") (pintype "passive"))
      (node (ref "C3") (pin "2") (pinfunction "2_2") (pintype "passive"))
      (node (ref "C301") (pin "2") (pinfunction "2_2") (pintype "passive"))
      (node (ref "C302") (pin "2") (pinfunction "2_2") (pintype "passive"))
      (node (ref "C303") (pin "2") (pinfunction "2_2") (pintype "passive"))
      (node (ref "C304") (pin "2") (pinfunction "2_2") (pintype "passive"))
      (node (ref "C305") (pin "2") (pinfunction "2_2") (pintype "passive"))
      (node (ref "C306") (pin "2") (pinfunction "2_2") (pintype "passive"))
      (node (ref "C308") (pin "2") (pinfunction "2_2") (pintype "passive"))
      (node (ref "C309") (pin "2") (pinfunction "2_2") (pintype "passive"))
      (node (ref "C4") (pin "2") (pinfunction "2_2") (pintype "passive"))
      (node (ref "C5") (pin "2") (pinfunction "2_2") (pintype "passive"))
      (node (ref "C6") (pin "2") (pinfunction "2_2") (pintype "passive"))
      (node (ref "C7") (pin "2") (pinfunction "2_2") (pintype "passive"))
      (node (ref "C8") (pin "2") (pinfunction "2_2") (pintype "passive"))
      (node (ref "C801") (pin "-") (pinfunction "-_-") (pintype "passive"))
      (node (ref "C802") (pin "-") (pinfunction "-_-") (pintype "passive"))
      (node (ref "C9") (pin "2") (pinfunction "2_2") (pintype "passive"))
      (node (ref "HP") (pin "2") (pinfunction "2_2") (pintype "passive"))
      (node (ref "IC1") (pin "1") (pinfunction "GND_1") (pintype "power_in"))
      (node (ref "IC3") (pin "12") (pinfunction "GND_12") (pintype "power_in"))
      (node (ref "IC3") (pin "34") (pinfunction "GND_34") (pintype "power_in"))
      (node (ref "IN") (pin "2") (pinfunction "2_2") (pintype "passive"))
      (node (ref "LED1") (pin "C") (pinfunction "C_C") (pintype "passive"))
      (node (ref "LED2") (pin "C") (pinfunction "C_C") (pintype "passive"))
      (node (ref "MIC") (pin "2") (pinfunction "2_2") (pintype "passive"))
      (node (ref "OUT") (pin "2") (pinfunction "2_2") (pintype "passive"))
      (node (ref "PWR") (pin "2") (pinfunction "2_2") (pintype "passive"))
      (node (ref "R9") (pin "2") (pinfunction "2_2") (pintype "passive"))
      (node (ref "SWD") (pin "3") (pinfunction "3_3") (pintype "passive"))
      (node (ref "U2") (pin "P$11") (pinfunction "HPGND_P$11") (pintype "power_in"))
      (node (ref "U2") (pin "P$15") (pinfunction "AGND_P$15") (pintype "power_in"))
      (node (ref "U2") (pin "P$21") (pinfunction "MODE_P$21") (pintype "input"))
      (node (ref "U2") (pin "P$22") (pinfunction "CSB_P$22") (pintype "input"))
      (node (ref "U2") (pin "P$28") (pinfunction "DGND_P$28") (pintype "power_in"))
      (node (ref "U4") (pin "107") (pinfunction "VSS_5_107") (pintype "power_in"))
      (node (ref "U4") (pin "120") (pinfunction "VSS_120") (pintype "power_in"))
      (node (ref "U4") (pin "130") (pinfunction "VSS_2_130") (pintype "power_in"))
      (node (ref "U4") (pin "17") (pinfunction "VSS_2_17") (pintype "power_in"))
      (node (ref "U4") (pin "31") (pinfunction "VSSA_31") (pintype "power_in"))
      (node (ref "U4") (pin "38") (pinfunction "VSS_3_38") (pintype "power_in"))
      (node (ref "U4") (pin "51") (pinfunction "VSS_4_51") (pintype "power_in"))
      (node (ref "U4") (pin "61") (pinfunction "VSS_61") (pintype "power_in"))
      (node (ref "U4") (pin "83") (pinfunction "VSS_3_83") (pintype "power_in"))
      (node (ref "U4") (pin "94") (pinfunction "VSS_4_94") (pintype "power_in"))
      (node (ref "UART") (pin "1") (pinfunction "1_1") (pintype "passive"))
      (node (ref "USB") (pin "5") (pinfunction "5_5") (pintype "passive"))
      (node (ref "USB1") (pin "5") (pinfunction "GND_5") (pintype "bidirectional"))
      (node (ref "USB1") (pin "G") (pinfunction "SHIELD_G") (pintype "bidirectional"))
      (node (ref "USB1") (pin "G2") (pinfunction "SHIELD_G2") (pintype "bidirectional"))
      (node (ref "USB1") (pin "G3") (pinfunction "SHIELD_G3") (pintype "bidirectional"))
      (node (ref "USB1") (pin "G4") (pinfunction "SHIELD_G4") (pintype "bidirectional"))
    )
    (net (code "106") (name "Net-(LED1-PadA)") (class "Default")
      (node (ref "LED1") (pin "A") (pinfunction "A_A") (pintype "passive"))
      (node (ref "R11") (pin "2") (pinfunction "2_2") (pintype "passive"))
    )
    (net (code "107") (name "Net-(LED2-PadA)") (class "Default")
      (node (ref "LED2") (pin "A") (pinfunction "A_A") (pintype "passive"))
      (node (ref "R12") (pin "2") (pinfunction "2_2") (pintype "passive"))
    )
    (net (code "108") (name "Net-(U2-LHPOUT)") (class "Default")
      (node (ref "HP") (pin "3") (pinfunction "3_3") (pintype "passive"))
      (node (ref "U2") (pin "P$9") (pinfunction "LHPOUT_P$9") (pintype "output"))
    )
    (net (code "109") (name "Net-(U2-MICBIAS)") (class "Default")
      (node (ref "MIC") (pin "3") (pinfunction "3_3") (pintype "passive"))
      (node (ref "U2") (pin "P$17") (pinfunction "MICBIAS_P$17") (pintype "output"))
    )
    (net (code "110") (name "Net-(U2-MICIN)") (class "Default")
      (node (ref "MIC") (pin "1") (pinfunction "1_1") (pintype "passive"))
      (node (ref "U2") (pin "P$18") (pinfunction "MICIN_P$18") (pintype "input"))
    )
    (net (code "111") (name "Net-(U2-RHPOUT)") (class "Default")
      (node (ref "HP") (pin "1") (pinfunction "1_1") (pintype "passive"))
      (node (ref "U2") (pin "P$10") (pinfunction "RHPOUT_P$10") (pintype "output"))
    )
    (net (code "112") (name "Net-(U4A-PH0)") (class "Default")
      (node (ref "C22") (pin "1") (pinfunction "1_1") (pintype "passive"))
      (node (ref "Q2") (pin "1") (pinfunction "1_1") (pintype "passive"))
      (node (ref "U4") (pin "23") (pinfunction "PH0_23") (pintype "bidirectional"))
    )
    (net (code "113") (name "Net-(U4A-PH1)") (class "Default")
      (node (ref "C23") (pin "1") (pinfunction "1_1") (pintype "passive"))
      (node (ref "Q2") (pin "2") (pinfunction "2_2") (pintype "passive"))
      (node (ref "U4") (pin "24") (pinfunction "PH1_24") (pintype "bidirectional"))
    )
    (net (code "114") (name "Net-(U4A-VCAP_1)") (class "Default")
      (node (ref "C20") (pin "2") (pinfunction "2_2") (pintype "passive"))
      (node (ref "U4") (pin "71") (pinfunction "VCAP_1_71") (pintype "passive"))
    )
    (net (code "115") (name "Net-(U4B-VCAP_2)") (class "Default")
      (node (ref "C21") (pin "1") (pinfunction "1_1") (pintype "passive"))
      (node (ref "U4") (pin "106") (pinfunction "VCAP_2_106") (pintype "passive"))
    )
    (net (code "116") (name "Net-(USB1-D+)") (class "Default")
      (node (ref "R4") (pin "1") (pinfunction "1_1") (pintype "passive"))
      (node (ref "USB1") (pin "3") (pinfunction "D+_3") (pintype "bidirectional"))
    )
    (net (code "117") (name "Net-(USB1-D-)") (class "Default")
      (node (ref "R5") (pin "1") (pinfunction "1_1") (pintype "passive"))
      (node (ref "USB1") (pin "2") (pinfunction "D-_2") (pintype "bidirectional"))
    )
    (net (code "118") (name "VCC{slash}2") (class "Default")
      (node (ref "C308") (pin "1") (pinfunction "1_1") (pintype "passive"))
      (node (ref "C309") (pin "1") (pinfunction "1_1") (pintype "passive"))
      (node (ref "U2") (pin "P$16") (pinfunction "VMID_P$16") (pintype "output"))
    )
    (net (code "119") (name "unconnected-(U2-XTO-PadP$26)") (class "Default")
      (node (ref "U2") (pin "P$26") (pinfunction "XTO_P$26") (pintype "output"))
    )
    (net (code "120") (name "unconnected-(U4A-PE2-Pad1)") (class "Default")
      (node (ref "U4") (pin "1") (pinfunction "PE2_1") (pintype "bidirectional"))
    )
    (net (code "121") (name "unconnected-(U4A-PE3-Pad2)") (class "Default")
      (node (ref "U4") (pin "2") (pinfunction "PE3_2") (pintype "bidirectional"))
    )
    (net (code "122") (name "unconnected-(U4A-PE4-Pad3)") (class "Default")
      (node (ref "U4") (pin "3") (pinfunction "PE4_3") (pintype "bidirectional"))
    )
    (net (code "123") (name "unconnected-(U4A-PE5-Pad4)") (class "Default")
      (node (ref "U4") (pin "4") (pinfunction "PE5_4") (pintype "bidirectional"))
    )
    (net (code "124") (name "unconnected-(U4A-PE6-Pad5)") (class "Default")
      (node (ref "U4") (pin "5") (pinfunction "PE6_5") (pintype "bidirectional"))
    )
    (net (code "125") (name "unconnected-(U4A-PF6-Pad18)") (class "Default")
      (node (ref "U4") (pin "18") (pinfunction "PF6_18") (pintype "bidirectional"))
    )
    (net (code "126") (name "unconnected-(U4A-PF7-Pad19)") (class "Default")
      (node (ref "U4") (pin "19") (pinfunction "PF7_19") (pintype "bidirectional"))
    )
    (net (code "127") (name "unconnected-(U4A-PF8-Pad20)") (class "Default")
      (node (ref "U4") (pin "20") (pinfunction "PF8_20") (pintype "bidirectional"))
    )
    (net (code "128") (name "unconnected-(U4A-PF9-Pad21)") (class "Default")
      (node (ref "U4") (pin "21") (pinfunction "PF9_21") (pintype "bidirectional"))
    )
    (net (code "129") (name "unconnected-(U4A-PF10-Pad22)") (class "Default")
      (node (ref "U4") (pin "22") (pinfunction "PF10_22") (pintype "bidirectional"))
    )
    (net (code "130") (name "unconnected-(U4A-PF11-Pad49)") (class "Default")
      (node (ref "U4") (pin "49") (pinfunction "PF11_49") (pintype "bidirectional"))
    )
    (net (code "131") (name "unconnected-(U4B-PDR_ON-Pad143)") (class "Default")
      (node (ref "U4") (pin "143") (pinfunction "PDR_ON_143") (pintype "passive"))
    )
    (net (code "132") (name "unconnected-(U4B-PG6-Pad91)") (class "Default")
      (node (ref "U4") (pin "91") (pinfunction "PG6_91") (pintype "bidirectional"))
    )
    (net (code "133") (name "unconnected-(U4B-PG7-Pad92)") (class "Default")
      (node (ref "U4") (pin "92") (pinfunction "PG7_92") (pintype "bidirectional"))
    )
    (net (code "134") (name "unconnected-(U4B-PG8-Pad93)") (class "Default")
      (node (ref "U4") (pin "93") (pinfunction "PG8_93") (pintype "bidirectional"))
    )
    (net (code "135") (name "unconnected-(U4B-PG11-Pad126)") (class "Default")
      (node (ref "U4") (pin "126") (pinfunction "PG11_126") (pintype "bidirectional"))
    )
    (net (code "136") (name "unconnected-(U4B-PG12-Pad127)") (class "Default")
      (node (ref "U4") (pin "127") (pinfunction "PG12_127") (pintype "bidirectional"))
    )
    (net (code "137") (name "unconnected-(U4B-PG13-Pad128)") (class "Default")
      (node (ref "U4") (pin "128") (pinfunction "PG13_128") (pintype "bidirectional"))
    )
    (net (code "138") (name "unconnected-(U4B-PG14-Pad129)") (class "Default")
      (node (ref "U4") (pin "129") (pinfunction "PG14_129") (pintype "bidirectional"))
    )
    (net (code "139") (name "unconnected-(U4B-PG15-Pad132)") (class "Default")
      (node (ref "U4") (pin "132") (pinfunction "PG15_132") (pintype "bidirectional"))
    )
    (net (code "140") (name "unconnected-(UART-Pad2)") (class "Default")
      (node (ref "UART") (pin "2") (pinfunction "2_2") (pintype "passive"))
    )
    (net (code "141") (name "unconnected-(UART-Pad3)") (class "Default")
      (node (ref "UART") (pin "3") (pinfunction "3_3") (pintype "passive"))
    )
    (net (code "142") (name "unconnected-(UART-Pad6)") (class "Default")
      (node (ref "UART") (pin "6") (pinfunction "6_6") (pintype "passive"))
    )
  )
)
